# nbiot_gps.net
KiCad netlist of a schematic drawn in Altium Designer
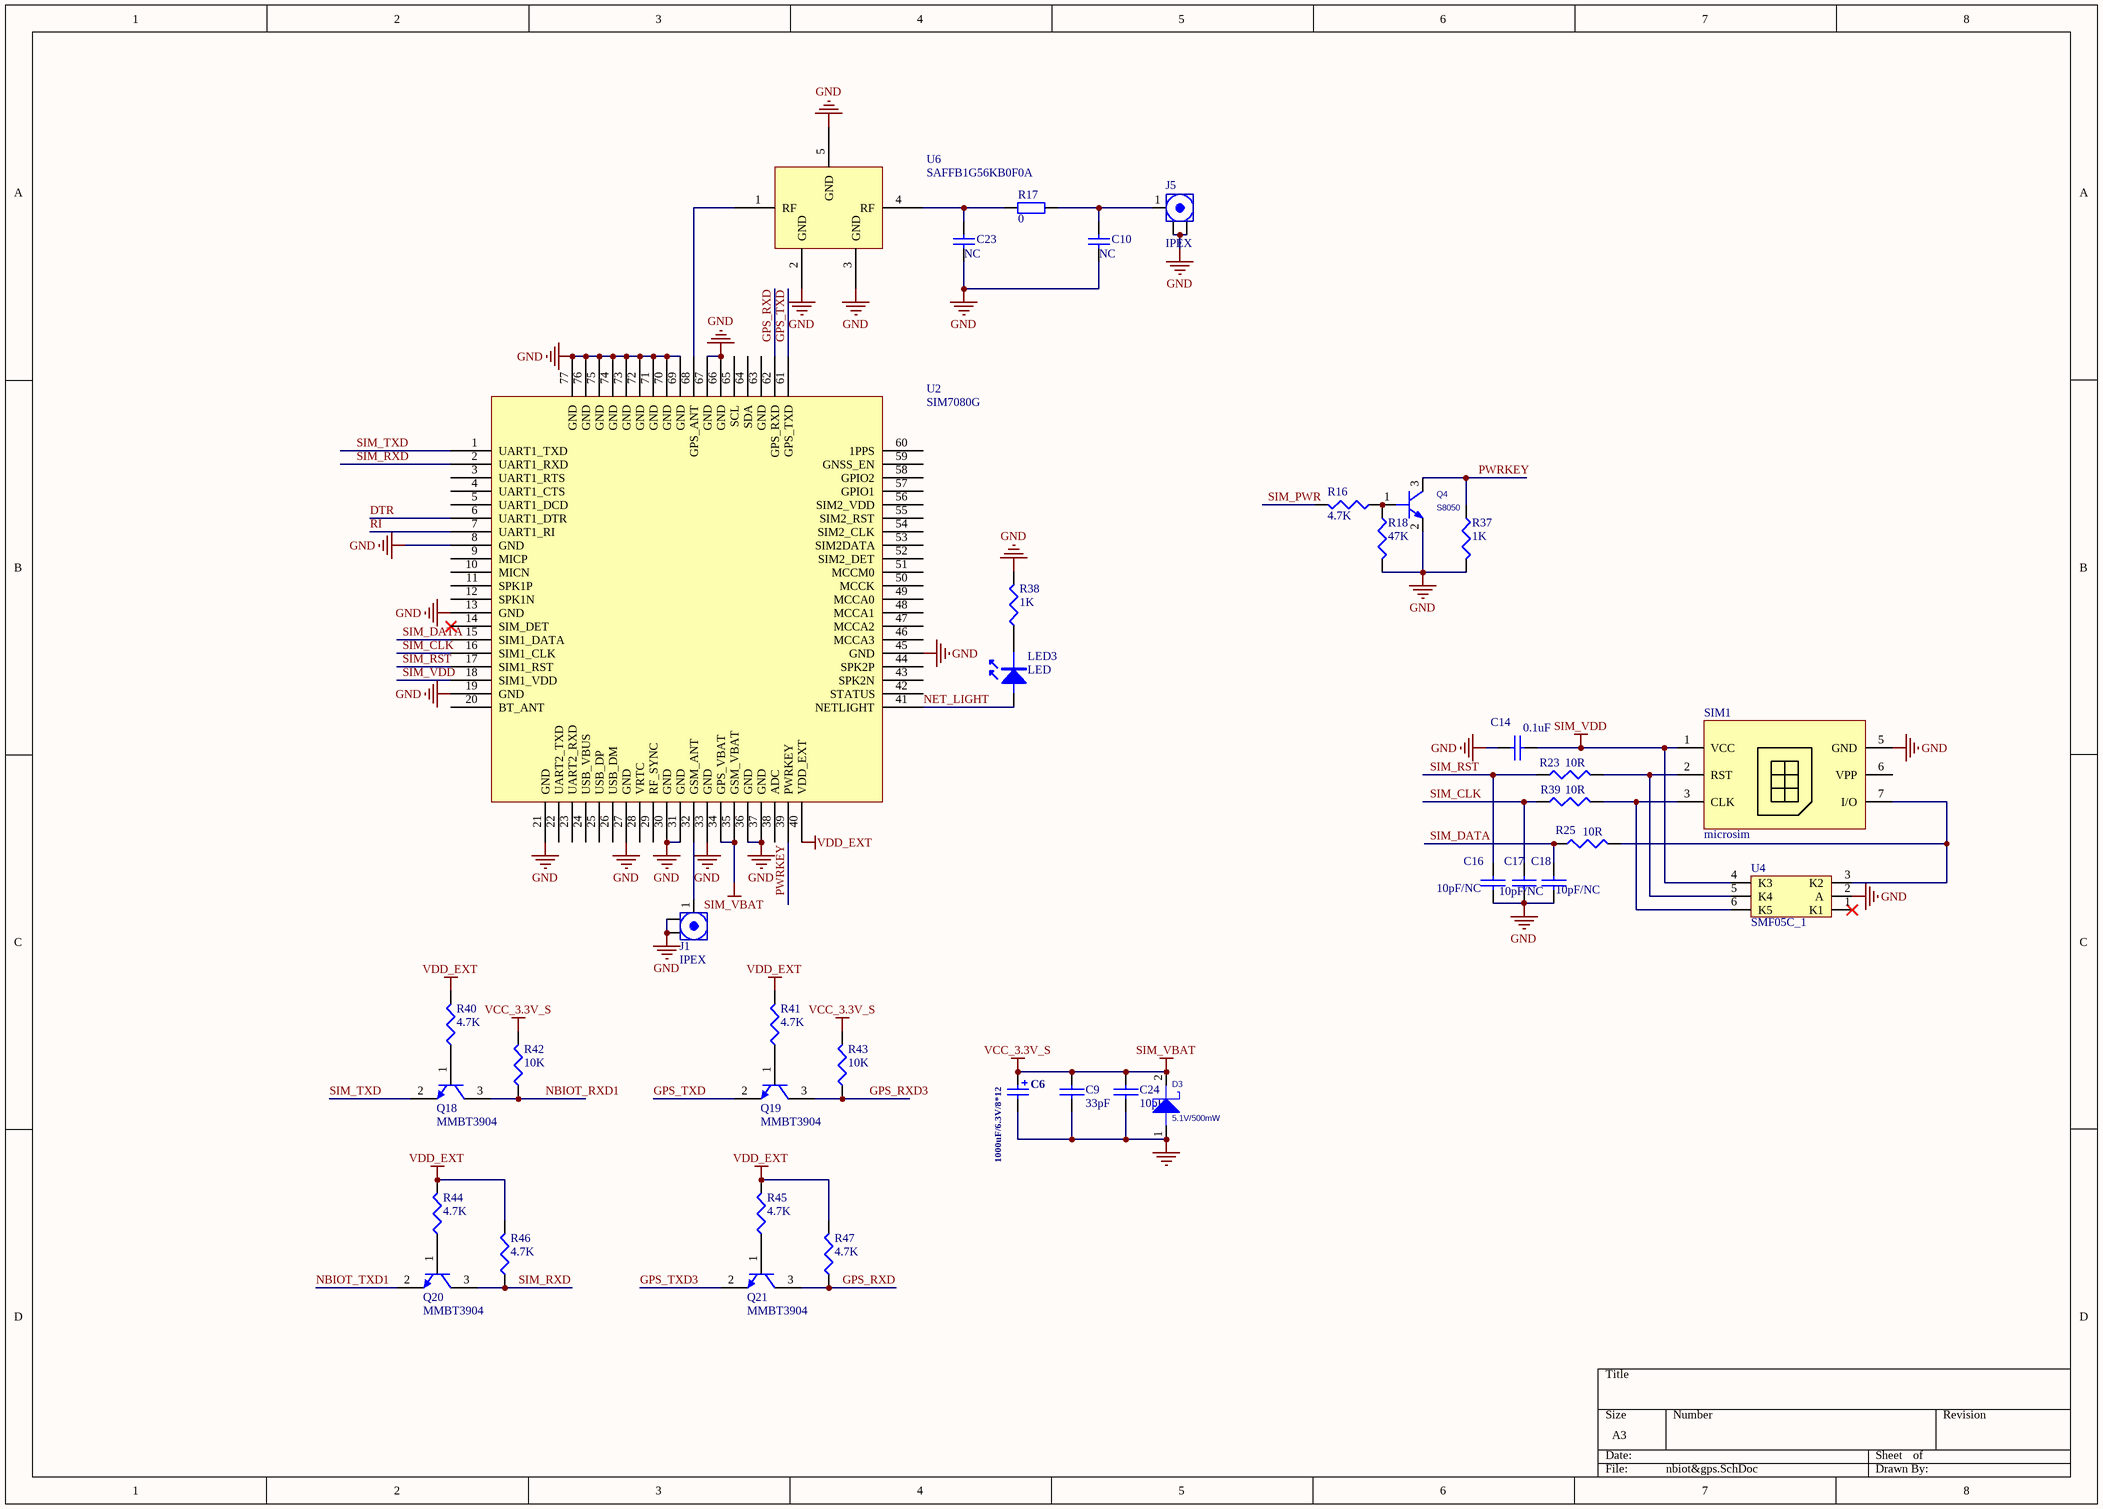
[diagram p0: nbiot&gps.SchDoc]

(export (version "E")
  (design (tool "Eeschema 10.0.6"))
  (components
    (comp (ref "C6")
      (value "1000uF/6.3V/8*12")
      (footprint "8*12")
      (description "Polarized Capacitor (Surface Mount)")
      (libsource (lib "KT_iBeacon") (part "Cap Pol3"))
    )
    (comp (ref "C9")
      (value "33pF")
      (footprint "0603C")
      (description "Capacitor")
      (libsource (lib "ZWLIntegrated_Library") (part "CAP"))
    )
    (comp (ref "C10")
      (value "NC")
      (footprint "0603C")
      (description "Capacitor")
      (fields (field (name "PUBLISHER") "Altium Limited"))
      (libsource (lib "Miscellaneous Devices") (part "Cap"))
    )
    (comp (ref "C14")
      (value "0.1uF")
      (footprint "0603C")
      (description "Capacitor")
      (libsource (lib "ZWLIntegrated_Library") (part "CAP"))
    )
    (comp (ref "C16")
      (value "10pF/NC")
      (footprint "0603C")
      (description "Capacitor")
      (libsource (lib "ZWLIntegrated_Library") (part "CAP"))
    )
    (comp (ref "C17")
      (value "10pF/NC")
      (footprint "0603C")
      (description "Capacitor")
      (libsource (lib "ZWLIntegrated_Library") (part "CAP"))
    )
    (comp (ref "C18")
      (value "10pF/NC")
      (footprint "0603C")
      (description "Capacitor")
      (libsource (lib "ZWLIntegrated_Library") (part "CAP"))
    )
    (comp (ref "C23")
      (value "NC")
      (footprint "0603C")
      (description "Capacitor")
      (fields (field (name "PUBLISHER") "Altium Limited"))
      (libsource (lib "Miscellaneous Devices") (part "Cap"))
    )
    (comp (ref "C24")
      (value "10pF")
      (footprint "0603C")
      (description "Capacitor")
      (libsource (lib "ZWLIntegrated_Library") (part "CAP"))
    )
    (comp (ref "D3")
      (value "5.1V/500mW")
      (footprint "LL-34(D1206)")
      (fields (field (name "Comment") "DIODE_SCHOTTKY_0"))
      (libsource (lib "KT_iBeacon") (part "DIODE_SCHOTTKY_0"))
    )
    (comp (ref "J1") (value "IPEX") (footprint "RF-UFL") (libsource (lib "我的元件库") (part "ANT")))
    (comp (ref "J5") (value "IPEX") (footprint "RF-UFL") (libsource (lib "我的元件库") (part "ANT")))
    (comp (ref "LED3") (value "LED") (footprint "0603LED") (libsource (lib "我的元件库") (part "LED")))
    (comp (ref "Q4") (value "S8050") (footprint "SOT23") (libsource (lib "*") (part "2N1069_1")))
    (comp (ref "Q18") (value "MMBT3904") (footprint "SOT23-3") (libsource (lib "Schlib1") (part "NPN")))
    (comp (ref "Q19") (value "MMBT3904") (footprint "SOT23-3") (libsource (lib "Schlib1") (part "NPN")))
    (comp (ref "Q20") (value "MMBT3904") (footprint "SOT23-3") (libsource (lib "Schlib1") (part "NPN")))
    (comp (ref "Q21") (value "MMBT3904") (footprint "SOT23-3") (libsource (lib "Schlib1") (part "NPN")))
    (comp (ref "R16")
      (value "4.7K")
      (footprint "0603R")
      (libsource (lib "ZWLIntegrated_Library") (part "RES1"))
    )
    (comp (ref "R17")
      (value "0")
      (footprint "0603R")
      (description "Resistor")
      (fields (field (name "PUBLISHER") "Altium Limited"))
      (libsource (lib "Miscellaneous Devices") (part "Res2"))
    )
    (comp (ref "R18")
      (value "47K")
      (footprint "0603R")
      (libsource (lib "ZWLIntegrated_Library") (part "RES1"))
    )
    (comp (ref "R23")
      (value "10R")
      (footprint "0603R")
      (libsource (lib "ZWLIntegrated_Library") (part "RES1"))
    )
    (comp (ref "R25")
      (value "10R")
      (footprint "0603R")
      (libsource (lib "ZWLIntegrated_Library") (part "RES1"))
    )
    (comp (ref "R37")
      (value "1K")
      (footprint "0603R")
      (libsource (lib "ZWLIntegrated_Library") (part "RES1"))
    )
    (comp (ref "R38")
      (value "1K")
      (footprint "0603R")
      (libsource (lib "ZWLIntegrated_Library") (part "RES1"))
    )
    (comp (ref "R39")
      (value "10R")
      (footprint "0603R")
      (libsource (lib "ZWLIntegrated_Library") (part "RES1"))
    )
    (comp (ref "R40")
      (value "4.7K")
      (footprint "0603R")
      (libsource (lib "ZWLIntegrated_Library") (part "RES1"))
    )
    (comp (ref "R41")
      (value "4.7K")
      (footprint "0603R")
      (libsource (lib "ZWLIntegrated_Library") (part "RES1"))
    )
    (comp (ref "R42")
      (value "10K")
      (footprint "0603R")
      (libsource (lib "ZWLIntegrated_Library") (part "RES1"))
    )
    (comp (ref "R43")
      (value "10K")
      (footprint "0603R")
      (libsource (lib "ZWLIntegrated_Library") (part "RES1"))
    )
    (comp (ref "R44")
      (value "4.7K")
      (footprint "0603R")
      (libsource (lib "ZWLIntegrated_Library") (part "RES1"))
    )
    (comp (ref "R45")
      (value "4.7K")
      (footprint "0603R")
      (libsource (lib "ZWLIntegrated_Library") (part "RES1"))
    )
    (comp (ref "R46")
      (value "4.7K")
      (footprint "0603R")
      (libsource (lib "ZWLIntegrated_Library") (part "RES1"))
    )
    (comp (ref "R47")
      (value "4.7K")
      (footprint "0603R")
      (libsource (lib "ZWLIntegrated_Library") (part "RES1"))
    )
    (comp (ref "SIM1")
      (value "microsim")
      (footprint "Nano SIM")
      (libsource (lib "SIM800C 原理图库") (part "microsim"))
    )
    (comp (ref "U2")
      (value "SIM7080G")
      (footprint "SIM868")
      (libsource (lib "stm32") (part "SIM868E/SIM868"))
    )
    (comp (ref "U4")
      (value "SMF05C_1")
      (footprint "SC70-6L")
      (description "TVS")
      (libsource (lib "SIM800C 原理图库") (part "SMF05C_1"))
    )
    (comp (ref "U6")
      (value "SAFFB1G56KB0F0A")
      (footprint "SAFFB1G56KB0F0A")
      (libsource (lib "stm32") (part "SAFFB1G56KBOFA"))
    )
  )
  (nets
    (net (code "1") (name "/DTR") (class "Default")
      (node (ref "U2") (pin "6") (pinfunction "UART1_DTR_6") (pintype "passive"))
    )
    (net (code "2") (name "/GPS_RXD") (class "Default")
      (node (ref "Q21") (pin "3") (pinfunction "C_3") (pintype "passive"))
      (node (ref "R47") (pin "1") (pinfunction "1_1") (pintype "passive"))
      (node (ref "U2") (pin "62") (pinfunction "GPS_RXD_62") (pintype "passive"))
    )
    (net (code "3") (name "/GPS_RXD3") (class "Default")
      (node (ref "Q19") (pin "3") (pinfunction "C_3") (pintype "passive"))
      (node (ref "R43") (pin "1") (pinfunction "1_1") (pintype "passive"))
    )
    (net (code "4") (name "/GPS_TXD") (class "Default")
      (node (ref "Q19") (pin "2") (pinfunction "E_2") (pintype "passive"))
      (node (ref "U2") (pin "61") (pinfunction "GPS_TXD_61") (pintype "passive"))
    )
    (net (code "5") (name "/GPS_TXD3") (class "Default")
      (node (ref "Q21") (pin "2") (pinfunction "E_2") (pintype "passive"))
    )
    (net (code "6") (name "/NBIOT_RXD1") (class "Default")
      (node (ref "Q18") (pin "3") (pinfunction "C_3") (pintype "passive"))
      (node (ref "R42") (pin "1") (pinfunction "1_1") (pintype "passive"))
    )
    (net (code "7") (name "/NBIOT_TXD1") (class "Default")
      (node (ref "Q20") (pin "2") (pinfunction "E_2") (pintype "passive"))
    )
    (net (code "8") (name "/NET_LIGHT") (class "Default")
      (node (ref "LED3") (pin "1") (pinfunction "1_1") (pintype "passive"))
      (node (ref "U2") (pin "41") (pinfunction "NETLIGHT_41") (pintype "passive"))
    )
    (net (code "9") (name "/PWRKEY") (class "Default")
      (node (ref "Q4") (pin "3") (pinfunction "C_3") (pintype "passive"))
      (node (ref "R37") (pin "1") (pinfunction "1_1") (pintype "passive"))
      (node (ref "U2") (pin "39") (pinfunction "PWRKEY_39") (pintype "passive"))
    )
    (net (code "10") (name "/RI") (class "Default")
      (node (ref "U2") (pin "7") (pinfunction "UART1_RI_7") (pintype "passive"))
    )
    (net (code "11") (name "/SIM_CLK") (class "Default")
      (node (ref "C17") (pin "2") (pinfunction "2_2") (pintype "passive"))
      (node (ref "R39") (pin "1") (pinfunction "1_1") (pintype "passive"))
      (node (ref "U2") (pin "16") (pinfunction "SIM1_CLK_16") (pintype "passive"))
    )
    (net (code "12") (name "/SIM_DATA") (class "Default")
      (node (ref "C18") (pin "2") (pinfunction "2_2") (pintype "passive"))
      (node (ref "R25") (pin "1") (pinfunction "1_1") (pintype "passive"))
      (node (ref "U2") (pin "15") (pinfunction "SIM1_DATA_15") (pintype "passive"))
    )
    (net (code "13") (name "/SIM_PWR") (class "Default")
      (node (ref "R16") (pin "2") (pinfunction "2_2") (pintype "passive"))
    )
    (net (code "14") (name "/SIM_RST") (class "Default")
      (node (ref "C16") (pin "2") (pinfunction "2_2") (pintype "passive"))
      (node (ref "R23") (pin "1") (pinfunction "1_1") (pintype "passive"))
      (node (ref "U2") (pin "17") (pinfunction "SIM1_RST_17") (pintype "passive"))
    )
    (net (code "15") (name "/SIM_RXD") (class "Default")
      (node (ref "Q20") (pin "3") (pinfunction "C_3") (pintype "passive"))
      (node (ref "R46") (pin "1") (pinfunction "1_1") (pintype "passive"))
      (node (ref "U2") (pin "2") (pinfunction "UART1_RXD_2") (pintype "passive"))
    )
    (net (code "16") (name "/SIM_TXD") (class "Default")
      (node (ref "Q18") (pin "2") (pinfunction "E_2") (pintype "passive"))
      (node (ref "U2") (pin "1") (pinfunction "UART1_TXD_1") (pintype "passive"))
    )
    (net (code "17") (name "GND") (class "Default")
      (node (ref "C10") (pin "2") (pinfunction "2_2") (pintype "passive"))
      (node (ref "C14") (pin "1") (pinfunction "1_1") (pintype "passive"))
      (node (ref "C16") (pin "1") (pinfunction "1_1") (pintype "passive"))
      (node (ref "C17") (pin "1") (pinfunction "1_1") (pintype "passive"))
      (node (ref "C18") (pin "1") (pinfunction "1_1") (pintype "passive"))
      (node (ref "C23") (pin "2") (pinfunction "2_2") (pintype "passive"))
      (node (ref "C24") (pin "1") (pinfunction "1_1") (pintype "passive"))
      (node (ref "C6") (pin "2") (pinfunction "2_2") (pintype "passive"))
      (node (ref "C9") (pin "1") (pinfunction "1_1") (pintype "passive"))
      (node (ref "D3") (pin "1") (pinfunction "1_1") (pintype "passive"))
      (node (ref "J1") (pin "2") (pinfunction "Y_2") (pintype "passive"))
      (node (ref "J5") (pin "2") (pinfunction "Y_2") (pintype "passive"))
      (node (ref "Q4") (pin "2") (pinfunction "E_2") (pintype "passive"))
      (node (ref "R18") (pin "2") (pinfunction "2_2") (pintype "passive"))
      (node (ref "R37") (pin "2") (pinfunction "2_2") (pintype "passive"))
      (node (ref "R38") (pin "2") (pinfunction "2_2") (pintype "passive"))
      (node (ref "SIM1") (pin "5") (pinfunction "GND_5") (pintype "passive"))
      (node (ref "U2") (pin "13") (pinfunction "GND_13") (pintype "passive"))
      (node (ref "U2") (pin "19") (pinfunction "GND_19") (pintype "passive"))
      (node (ref "U2") (pin "21") (pinfunction "GND_21") (pintype "passive"))
      (node (ref "U2") (pin "27") (pinfunction "GND_27") (pintype "passive"))
      (node (ref "U2") (pin "30") (pinfunction "GND_30") (pintype "passive"))
      (node (ref "U2") (pin "31") (pinfunction "GND_31") (pintype "passive"))
      (node (ref "U2") (pin "33") (pinfunction "GND_33") (pintype "passive"))
      (node (ref "U2") (pin "36") (pinfunction "GND_36") (pintype "passive"))
      (node (ref "U2") (pin "37") (pinfunction "GND_37") (pintype "passive"))
      (node (ref "U2") (pin "45") (pinfunction "GND_45") (pintype "passive"))
      (node (ref "U2") (pin "66") (pinfunction "GND_66") (pintype "passive"))
      (node (ref "U2") (pin "67") (pinfunction "GND_67") (pintype "passive"))
      (node (ref "U2") (pin "69") (pinfunction "GND_69") (pintype "passive"))
      (node (ref "U2") (pin "70") (pinfunction "GND_70") (pintype "passive"))
      (node (ref "U2") (pin "71") (pinfunction "GND_71") (pintype "passive"))
      (node (ref "U2") (pin "72") (pinfunction "GND_72") (pintype "passive"))
      (node (ref "U2") (pin "73") (pinfunction "GND_73") (pintype "passive"))
      (node (ref "U2") (pin "74") (pinfunction "GND_74") (pintype "passive"))
      (node (ref "U2") (pin "75") (pinfunction "GND_75") (pintype "passive"))
      (node (ref "U2") (pin "76") (pinfunction "GND_76") (pintype "passive"))
      (node (ref "U2") (pin "77") (pinfunction "GND_77") (pintype "passive"))
      (node (ref "U2") (pin "8") (pinfunction "GND_8") (pintype "passive"))
      (node (ref "U4") (pin "2") (pinfunction "A_2") (pintype "passive"))
      (node (ref "U6") (pin "2") (pinfunction "GND_2") (pintype "passive"))
      (node (ref "U6") (pin "3") (pinfunction "GND_3") (pintype "passive"))
      (node (ref "U6") (pin "5") (pinfunction "GND_5") (pintype "passive"))
    )
    (net (code "18") (name "Net-(C23-Pad1)") (class "Default")
      (node (ref "C23") (pin "1") (pinfunction "1_1") (pintype "passive"))
      (node (ref "R17") (pin "1") (pinfunction "1_1") (pintype "passive"))
      (node (ref "U6") (pin "4") (pinfunction "RF_4") (pintype "passive"))
    )
    (net (code "19") (name "Net-(J1-X)") (class "Default")
      (node (ref "J1") (pin "1") (pinfunction "X_1") (pintype "passive"))
      (node (ref "U2") (pin "32") (pinfunction "GSM_ANT_32") (pintype "passive"))
    )
    (net (code "20") (name "Net-(J5-X)") (class "Default")
      (node (ref "C10") (pin "1") (pinfunction "1_1") (pintype "passive"))
      (node (ref "J5") (pin "1") (pinfunction "X_1") (pintype "passive"))
      (node (ref "R17") (pin "2") (pinfunction "2_2") (pintype "passive"))
    )
    (net (code "21") (name "Net-(LED3-Pad2)") (class "Default")
      (node (ref "LED3") (pin "2") (pinfunction "2_2") (pintype "passive"))
      (node (ref "R38") (pin "1") (pinfunction "1_1") (pintype "passive"))
    )
    (net (code "22") (name "Net-(Q4-B)") (class "Default")
      (node (ref "Q4") (pin "1") (pinfunction "B_1") (pintype "passive"))
      (node (ref "R16") (pin "1") (pinfunction "1_1") (pintype "passive"))
      (node (ref "R18") (pin "1") (pinfunction "1_1") (pintype "passive"))
    )
    (net (code "23") (name "Net-(Q18-B)") (class "Default")
      (node (ref "Q18") (pin "1") (pinfunction "B_1") (pintype "passive"))
      (node (ref "R40") (pin "1") (pinfunction "1_1") (pintype "passive"))
    )
    (net (code "24") (name "Net-(Q19-B)") (class "Default")
      (node (ref "Q19") (pin "1") (pinfunction "B_1") (pintype "passive"))
      (node (ref "R41") (pin "1") (pinfunction "1_1") (pintype "passive"))
    )
    (net (code "25") (name "Net-(Q20-B)") (class "Default")
      (node (ref "Q20") (pin "1") (pinfunction "B_1") (pintype "passive"))
      (node (ref "R44") (pin "1") (pinfunction "1_1") (pintype "passive"))
    )
    (net (code "26") (name "Net-(Q21-B)") (class "Default")
      (node (ref "Q21") (pin "1") (pinfunction "B_1") (pintype "passive"))
      (node (ref "R45") (pin "1") (pinfunction "1_1") (pintype "passive"))
    )
    (net (code "27") (name "Net-(SIM1-CLK)") (class "Default")
      (node (ref "R39") (pin "2") (pinfunction "2_2") (pintype "passive"))
      (node (ref "SIM1") (pin "3") (pinfunction "CLK_3") (pintype "passive"))
      (node (ref "U4") (pin "6") (pinfunction "K5_6") (pintype "passive"))
    )
    (net (code "28") (name "Net-(SIM1-I{slash}O)") (class "Default")
      (node (ref "R25") (pin "2") (pinfunction "2_2") (pintype "passive"))
      (node (ref "SIM1") (pin "7") (pinfunction "I/O_7") (pintype "passive"))
      (node (ref "U4") (pin "3") (pinfunction "K2_3") (pintype "passive"))
    )
    (net (code "29") (name "Net-(SIM1-RST)") (class "Default")
      (node (ref "R23") (pin "2") (pinfunction "2_2") (pintype "passive"))
      (node (ref "SIM1") (pin "2") (pinfunction "RST_2") (pintype "passive"))
      (node (ref "U4") (pin "5") (pinfunction "K4_5") (pintype "passive"))
    )
    (net (code "30") (name "Net-(U2-GPS_ANT)") (class "Default")
      (node (ref "U2") (pin "68") (pinfunction "GPS_ANT_68") (pintype "passive"))
      (node (ref "U6") (pin "1") (pinfunction "RF_1") (pintype "passive"))
    )
    (net (code "31") (name "SIM_VBAT") (class "Default")
      (node (ref "C24") (pin "2") (pinfunction "2_2") (pintype "passive"))
      (node (ref "C6") (pin "1") (pinfunction "1_1") (pintype "passive"))
      (node (ref "C9") (pin "2") (pinfunction "2_2") (pintype "passive"))
      (node (ref "D3") (pin "2") (pinfunction "2_2") (pintype "passive"))
      (node (ref "R42") (pin "2") (pinfunction "2_2") (pintype "passive"))
      (node (ref "R43") (pin "2") (pinfunction "2_2") (pintype "passive"))
      (node (ref "U2") (pin "34") (pinfunction "GPS_VBAT_34") (pintype "passive"))
      (node (ref "U2") (pin "35") (pinfunction "GSM_VBAT_35") (pintype "passive"))
    )
    (net (code "32") (name "SIM_VDD") (class "Default")
      (node (ref "C14") (pin "2") (pinfunction "2_2") (pintype "passive"))
      (node (ref "SIM1") (pin "1") (pinfunction "VCC_1") (pintype "passive"))
      (node (ref "U2") (pin "18") (pinfunction "SIM1_VDD_18") (pintype "passive"))
      (node (ref "U4") (pin "4") (pinfunction "K3_4") (pintype "passive"))
    )
    (net (code "33") (name "VDD_EXT") (class "Default")
      (node (ref "R40") (pin "2") (pinfunction "2_2") (pintype "passive"))
      (node (ref "R41") (pin "2") (pinfunction "2_2") (pintype "passive"))
      (node (ref "R44") (pin "2") (pinfunction "2_2") (pintype "passive"))
      (node (ref "R45") (pin "2") (pinfunction "2_2") (pintype "passive"))
      (node (ref "R46") (pin "2") (pinfunction "2_2") (pintype "passive"))
      (node (ref "R47") (pin "2") (pinfunction "2_2") (pintype "passive"))
      (node (ref "U2") (pin "40") (pinfunction "VDD_EXT_40") (pintype "passive"))
    )
    (net (code "34") (name "unconnected-(SIM1-VPP-Pad6)") (class "Default")
      (node (ref "SIM1") (pin "6") (pinfunction "VPP_6") (pintype "passive"))
    )
    (net (code "35") (name "unconnected-(U2-1PPS-Pad60)") (class "Default")
      (node (ref "U2") (pin "60") (pinfunction "1PPS_60") (pintype "passive"))
    )
    (net (code "36") (name "unconnected-(U2-ADC-Pad38)") (class "Default")
      (node (ref "U2") (pin "38") (pinfunction "ADC_38") (pintype "passive"))
    )
    (net (code "37") (name "unconnected-(U2-BT_ANT-Pad20)") (class "Default")
      (node (ref "U2") (pin "20") (pinfunction "BT_ANT_20") (pintype "passive"))
    )
    (net (code "38") (name "unconnected-(U2-GND-Pad63)") (class "Default")
      (node (ref "U2") (pin "63") (pinfunction "GND_63") (pintype "passive"))
    )
    (net (code "39") (name "unconnected-(U2-GNSS_EN-Pad59)") (class "Default")
      (node (ref "U2") (pin "59") (pinfunction "GNSS_EN_59") (pintype "passive"))
    )
    (net (code "40") (name "unconnected-(U2-GPIO1-Pad57)") (class "Default")
      (node (ref "U2") (pin "57") (pinfunction "GPIO1_57") (pintype "passive"))
    )
    (net (code "41") (name "unconnected-(U2-GPIO2-Pad58)") (class "Default")
      (node (ref "U2") (pin "58") (pinfunction "GPIO2_58") (pintype "passive"))
    )
    (net (code "42") (name "unconnected-(U2-MCCA0-Pad49)") (class "Default")
      (node (ref "U2") (pin "49") (pinfunction "MCCA0_49") (pintype "passive"))
    )
    (net (code "43") (name "unconnected-(U2-MCCA1-Pad48)") (class "Default")
      (node (ref "U2") (pin "48") (pinfunction "MCCA1_48") (pintype "passive"))
    )
    (net (code "44") (name "unconnected-(U2-MCCA2-Pad47)") (class "Default")
      (node (ref "U2") (pin "47") (pinfunction "MCCA2_47") (pintype "passive"))
    )
    (net (code "45") (name "unconnected-(U2-MCCA3-Pad46)") (class "Default")
      (node (ref "U2") (pin "46") (pinfunction "MCCA3_46") (pintype "passive"))
    )
    (net (code "46") (name "unconnected-(U2-MCCK-Pad50)") (class "Default")
      (node (ref "U2") (pin "50") (pinfunction "MCCK_50") (pintype "passive"))
    )
    (net (code "47") (name "unconnected-(U2-MCCM0-Pad51)") (class "Default")
      (node (ref "U2") (pin "51") (pinfunction "MCCM0_51") (pintype "passive"))
    )
    (net (code "48") (name "unconnected-(U2-MICN-Pad10)") (class "Default")
      (node (ref "U2") (pin "10") (pinfunction "MICN_10") (pintype "passive"))
    )
    (net (code "49") (name "unconnected-(U2-MICP-Pad9)") (class "Default")
      (node (ref "U2") (pin "9") (pinfunction "MICP_9") (pintype "passive"))
    )
    (net (code "50") (name "unconnected-(U2-RF_SYNC-Pad29)") (class "Default")
      (node (ref "U2") (pin "29") (pinfunction "RF_SYNC_29") (pintype "passive"))
    )
    (net (code "51") (name "unconnected-(U2-SCL-Pad65)") (class "Default")
      (node (ref "U2") (pin "65") (pinfunction "SCL_65") (pintype "passive"))
    )
    (net (code "52") (name "unconnected-(U2-SDA-Pad64)") (class "Default")
      (node (ref "U2") (pin "64") (pinfunction "SDA_64") (pintype "passive"))
    )
    (net (code "53") (name "unconnected-(U2-SIM2DATA-Pad53)") (class "Default")
      (node (ref "U2") (pin "53") (pinfunction "SIM2DATA_53") (pintype "passive"))
    )
    (net (code "54") (name "unconnected-(U2-SIM2_CLK-Pad54)") (class "Default")
      (node (ref "U2") (pin "54") (pinfunction "SIM2_CLK_54") (pintype "passive"))
    )
    (net (code "55") (name "unconnected-(U2-SIM2_DET-Pad52)") (class "Default")
      (node (ref "U2") (pin "52") (pinfunction "SIM2_DET_52") (pintype "passive"))
    )
    (net (code "56") (name "unconnected-(U2-SIM2_RST-Pad55)") (class "Default")
      (node (ref "U2") (pin "55") (pinfunction "SIM2_RST_55") (pintype "passive"))
    )
    (net (code "57") (name "unconnected-(U2-SIM2_VDD-Pad56)") (class "Default")
      (node (ref "U2") (pin "56") (pinfunction "SIM2_VDD_56") (pintype "passive"))
    )
    (net (code "58") (name "unconnected-(U2-SIM_DET-Pad14)") (class "Default")
      (node (ref "U2") (pin "14") (pinfunction "SIM_DET_14") (pintype "passive+no_connect"))
    )
    (net (code "59") (name "unconnected-(U2-SPK1N-Pad12)") (class "Default")
      (node (ref "U2") (pin "12") (pinfunction "SPK1N_12") (pintype "passive"))
    )
    (net (code "60") (name "unconnected-(U2-SPK1P-Pad11)") (class "Default")
      (node (ref "U2") (pin "11") (pinfunction "SPK1P_11") (pintype "passive"))
    )
    (net (code "61") (name "unconnected-(U2-SPK2N-Pad43)") (class "Default")
      (node (ref "U2") (pin "43") (pinfunction "SPK2N_43") (pintype "passive"))
    )
    (net (code "62") (name "unconnected-(U2-SPK2P-Pad44)") (class "Default")
      (node (ref "U2") (pin "44") (pinfunction "SPK2P_44") (pintype "passive"))
    )
    (net (code "63") (name "unconnected-(U2-STATUS-Pad42)") (class "Default")
      (node (ref "U2") (pin "42") (pinfunction "STATUS_42") (pintype "passive"))
    )
    (net (code "64") (name "unconnected-(U2-UART1_CTS-Pad4)") (class "Default")
      (node (ref "U2") (pin "4") (pinfunction "UART1_CTS_4") (pintype "passive"))
    )
    (net (code "65") (name "unconnected-(U2-UART1_DCD-Pad5)") (class "Default")
      (node (ref "U2") (pin "5") (pinfunction "UART1_DCD_5") (pintype "passive"))
    )
    (net (code "66") (name "unconnected-(U2-UART1_RTS-Pad3)") (class "Default")
      (node (ref "U2") (pin "3") (pinfunction "UART1_RTS_3") (pintype "passive"))
    )
    (net (code "67") (name "unconnected-(U2-UART2_RXD-Pad23)") (class "Default")
      (node (ref "U2") (pin "23") (pinfunction "UART2_RXD_23") (pintype "passive"))
    )
    (net (code "68") (name "unconnected-(U2-UART2_TXD-Pad22)") (class "Default")
      (node (ref "U2") (pin "22") (pinfunction "UART2_TXD_22") (pintype "passive"))
    )
    (net (code "69") (name "unconnected-(U2-USB_DM-Pad26)") (class "Default")
      (node (ref "U2") (pin "26") (pinfunction "USB_DM_26") (pintype "passive"))
    )
    (net (code "70") (name "unconnected-(U2-USB_DP-Pad25)") (class "Default")
      (node (ref "U2") (pin "25") (pinfunction "USB_DP_25") (pintype "passive"))
    )
    (net (code "71") (name "unconnected-(U2-USB_VBUS-Pad24)") (class "Default")
      (node (ref "U2") (pin "24") (pinfunction "USB_VBUS_24") (pintype "passive"))
    )
    (net (code "72") (name "unconnected-(U2-VRTC-Pad28)") (class "Default")
      (node (ref "U2") (pin "28") (pinfunction "VRTC_28") (pintype "passive"))
    )
    (net (code "73") (name "unconnected-(U4-K1-Pad1)") (class "Default")
      (node (ref "U4") (pin "1") (pinfunction "K1_1") (pintype "passive+no_connect"))
    )
  )
)
